# SCH_ea-powerplant_2025-10-05.net
KiCad netlist of a schematic drawn in EasyEDA
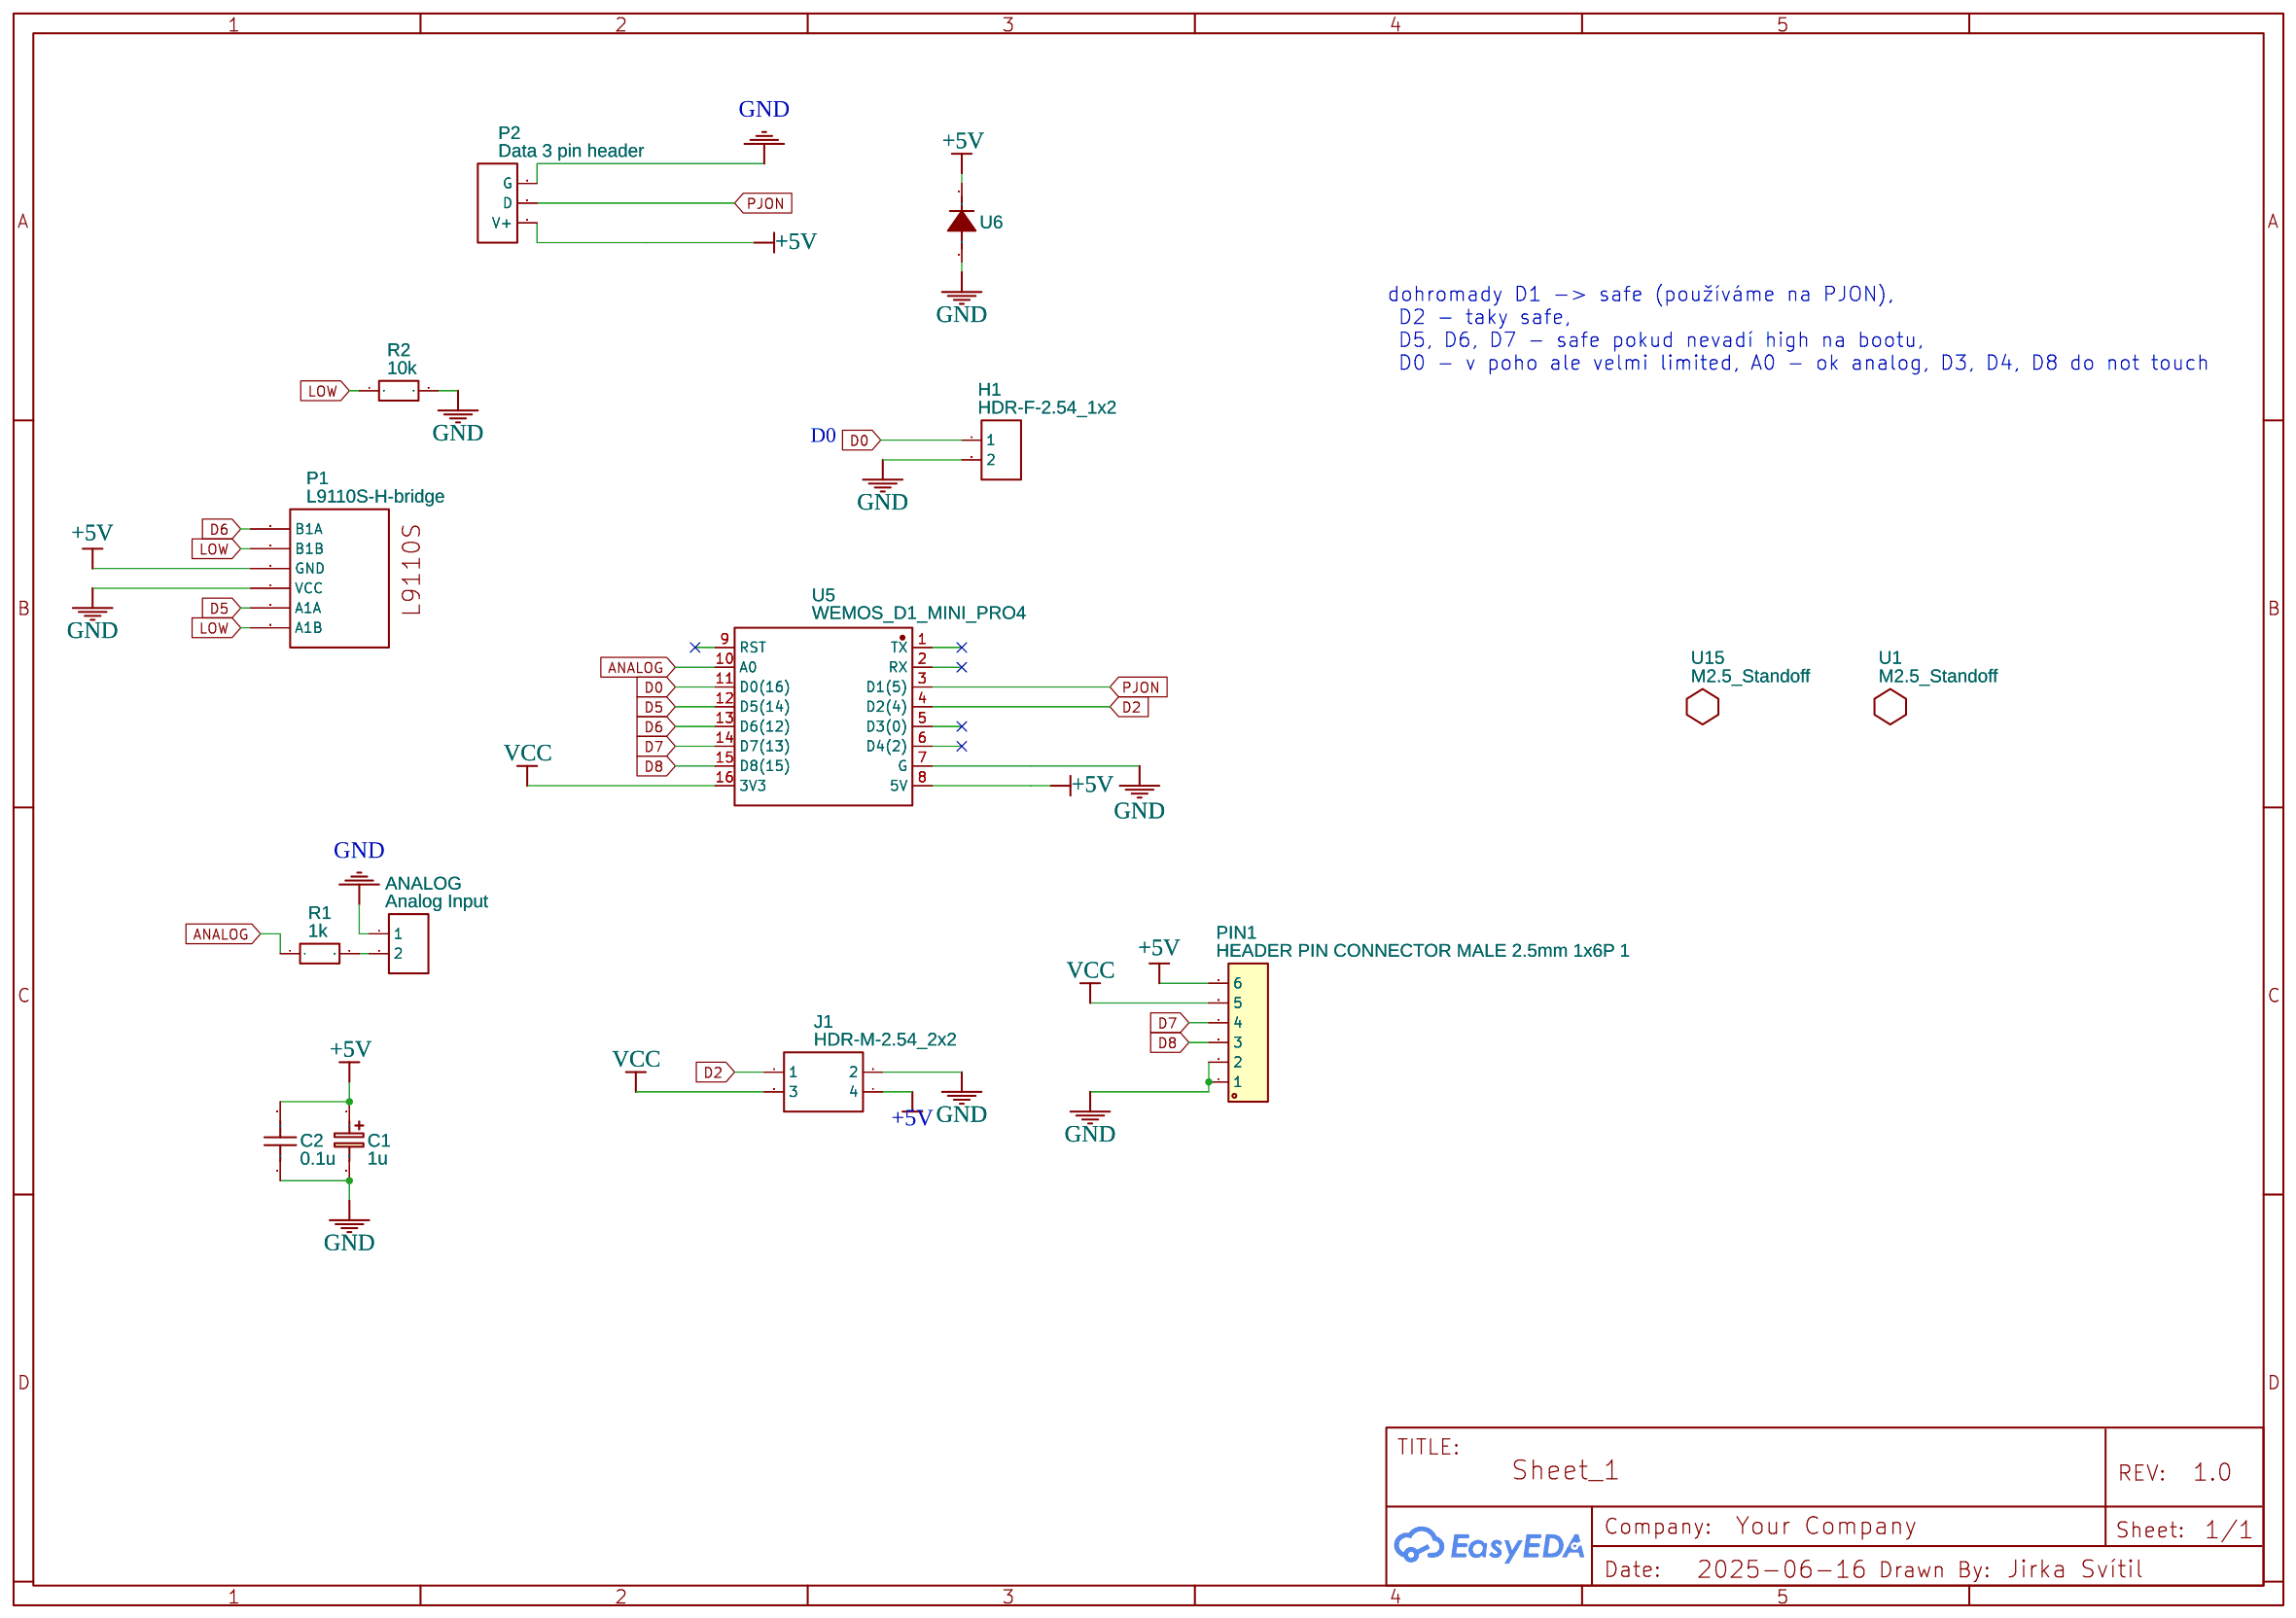
[diagram p0: schematic sheet]

(export (version "E")
  (design (tool "Eeschema 10.0.6"))
  (components
    (comp (ref "ANALOG") (value "Analog Input") (libsource (lib "") (part "HDR-F-2.54_1x2")))
    (comp (ref "C1") (value "1u") (libsource (lib "") (part "C_Tan_SMD_A_EU")))
    (comp (ref "C2") (value "0.1u") (libsource (lib "") (part "C_0603_US")))
    (comp (ref "H1") (value "HDR-F-2.54_1x2") (libsource (lib "") (part "HDR-F-2.54_1x2_1")))
    (comp (ref "J1") (value "HDR-M-2.54_2x2") (libsource (lib "") (part "HDR-M-2.54_2x2")))
    (comp (ref "P1")
      (value "L9110S-H-bridge")
      (fields
        (field (name "Manufacturer Part") "Header-Male-2.54_1x6")
        (field (name "Manufacturer") "BOOMELE")
      )
      (libsource (lib "") (part "Socket for L9110S-H-bridge-Stepper-Motor-Dual-DC-Motor-Driver-Controller-Module"))
    )
    (comp (ref "P2")
      (value "Data 3 pin header")
      (fields
        (field (name "Manufacturer Part") "Header-Female-2.54_1x3")
        (field (name "Manufacturer") "Boom Precision Elec")
      )
      (libsource (lib "") (part "Data 3 pin header"))
    )
    (comp (ref "PIN1")
      (value "HEADER PIN CONNECTOR MALE 2.5mm 1x6P 1")
      (libsource (lib "") (part "HEADER PIN CONNECTOR MALE 2.5mm 1x6P 1"))
    )
    (comp (ref "R1") (value "1k") (libsource (lib "") (part "R_0603_EU")))
    (comp (ref "R2") (value "10k") (libsource (lib "") (part "R_0603_EU")))
    (comp (ref "U1") (value "M2.5_Standoff") (libsource (lib "") (part "M2.5_Standoff")))
    (comp (ref "U5")
      (value "WEMOS_D1_MINI_PRO4")
      (fields (field (name "Manufacturer Part") "Wemos_D1_mini_Pro4"))
      (libsource (lib "") (part "WEMOS_D1_MINI_PRO4"))
    )
    (comp (ref "U6")
      (value "S3M_C4154420")
      (fields (field (name "Manufacturer Part") "S3M") (field (name "Manufacturer") "TWGMC(台湾迪嘉)"))
      (libsource (lib "") (part "S3M_C4154420"))
    )
    (comp (ref "U15") (value "M2.5_Standoff") (libsource (lib "") (part "M2.5_Standoff")))
  )
  (nets
    (net (code "1") (name "+5V") (class "Default")
      (node (ref "C1") (pin "1") (pinfunction "1_1") (pintype "unspecified"))
      (node (ref "C2") (pin "2") (pinfunction "2_2") (pintype "unspecified"))
      (node (ref "J1") (pin "4") (pinfunction "4_4") (pintype "input"))
      (node (ref "P1") (pin "3") (pinfunction "GND_3") (pintype "input"))
      (node (ref "P2") (pin "1") (pinfunction "V+_1") (pintype "input"))
      (node (ref "PIN1") (pin "6") (pinfunction "6_6") (pintype "unspecified"))
      (node (ref "U5") (pin "8") (pinfunction "5V_8") (pintype "unspecified"))
      (node (ref "U6") (pin "1") (pinfunction "1_1") (pintype "unspecified"))
    )
    (net (code "2") (name "ANALOG") (class "Default")
      (node (ref "R1") (pin "1") (pinfunction "1_1") (pintype "unspecified"))
      (node (ref "U5") (pin "10") (pinfunction "A0_10") (pintype "unspecified"))
    )
    (net (code "3") (name "D0") (class "Default")
      (node (ref "H1") (pin "1") (pinfunction "1_1") (pintype "input"))
      (node (ref "U5") (pin "11") (pinfunction "D0(16)_11") (pintype "unspecified"))
    )
    (net (code "4") (name "D2") (class "Default")
      (node (ref "J1") (pin "1") (pinfunction "1_1") (pintype "input"))
      (node (ref "U5") (pin "4") (pinfunction "D2(4)_4") (pintype "unspecified"))
    )
    (net (code "5") (name "D5") (class "Default")
      (node (ref "P1") (pin "5") (pinfunction "A1A_5") (pintype "input"))
      (node (ref "U5") (pin "12") (pinfunction "D5(14)_12") (pintype "unspecified"))
    )
    (net (code "6") (name "D6") (class "Default")
      (node (ref "P1") (pin "1") (pinfunction "B1A_1") (pintype "input"))
      (node (ref "U5") (pin "13") (pinfunction "D6(12)_13") (pintype "unspecified"))
    )
    (net (code "7") (name "D7") (class "Default")
      (node (ref "PIN1") (pin "4") (pinfunction "4_4") (pintype "unspecified"))
      (node (ref "U5") (pin "14") (pinfunction "D7(13)_14") (pintype "unspecified"))
    )
    (net (code "8") (name "D8") (class "Default")
      (node (ref "PIN1") (pin "3") (pinfunction "3_3") (pintype "unspecified"))
      (node (ref "U5") (pin "15") (pinfunction "D8(15)_15") (pintype "unspecified"))
    )
    (net (code "9") (name "GND") (class "Default")
      (node (ref "ANALOG") (pin "1") (pinfunction "1_1") (pintype "input"))
      (node (ref "C1") (pin "2") (pinfunction "2_2") (pintype "unspecified"))
      (node (ref "C2") (pin "1") (pinfunction "1_1") (pintype "unspecified"))
      (node (ref "H1") (pin "2") (pinfunction "2_2") (pintype "input"))
      (node (ref "J1") (pin "2") (pinfunction "2_2") (pintype "input"))
      (node (ref "P1") (pin "4") (pinfunction "VCC_4") (pintype "input"))
      (node (ref "P2") (pin "3") (pinfunction "G_3") (pintype "input"))
      (node (ref "PIN1") (pin "1") (pinfunction "1_1") (pintype "unspecified"))
      (node (ref "PIN1") (pin "2") (pinfunction "2_2") (pintype "unspecified"))
      (node (ref "R2") (pin "2") (pinfunction "2_2") (pintype "unspecified"))
      (node (ref "U5") (pin "7") (pinfunction "G_7") (pintype "unspecified"))
      (node (ref "U6") (pin "2") (pinfunction "2_2") (pintype "unspecified"))
    )
    (net (code "10") (name "LOW") (class "Default")
      (node (ref "P1") (pin "2") (pinfunction "B1B_2") (pintype "input"))
      (node (ref "P1") (pin "6") (pinfunction "A1B_6") (pintype "input"))
      (node (ref "R2") (pin "1") (pinfunction "1_1") (pintype "unspecified"))
    )
    (net (code "11") (name "Net-(ANALOG-Pad2)") (class "Default")
      (node (ref "ANALOG") (pin "2") (pinfunction "2_2") (pintype "input"))
      (node (ref "R1") (pin "2") (pinfunction "2_2") (pintype "unspecified"))
    )
    (net (code "12") (name "PJON") (class "Default")
      (node (ref "P2") (pin "2") (pinfunction "D_2") (pintype "input"))
      (node (ref "U5") (pin "3") (pinfunction "D1(5)_3") (pintype "unspecified"))
    )
    (net (code "13") (name "VCC") (class "Default")
      (node (ref "J1") (pin "3") (pinfunction "3_3") (pintype "input"))
      (node (ref "PIN1") (pin "5") (pinfunction "5_5") (pintype "unspecified"))
      (node (ref "U5") (pin "16") (pinfunction "3V3_16") (pintype "unspecified"))
    )
    (net (code "14") (name "unconnected-(U5-D3(0)-Pad5)") (class "Default")
      (node (ref "U5") (pin "5") (pinfunction "D3(0)_5") (pintype "unspecified+no_connect"))
    )
    (net (code "15") (name "unconnected-(U5-D4(2)-Pad6)") (class "Default")
      (node (ref "U5") (pin "6") (pinfunction "D4(2)_6") (pintype "unspecified+no_connect"))
    )
    (net (code "16") (name "unconnected-(U5-RST-Pad9)") (class "Default")
      (node (ref "U5") (pin "9") (pinfunction "RST_9") (pintype "unspecified+no_connect"))
    )
    (net (code "17") (name "unconnected-(U5-RX-Pad2)") (class "Default")
      (node (ref "U5") (pin "2") (pinfunction "RX_2") (pintype "unspecified+no_connect"))
    )
    (net (code "18") (name "unconnected-(U5-TX-Pad1)") (class "Default")
      (node (ref "U5") (pin "1") (pinfunction "TX_1") (pintype "unspecified+no_connect"))
    )
  )
)
